# 12_MT7688AN_Power.net
KiCad netlist of a schematic drawn in Altium Designer
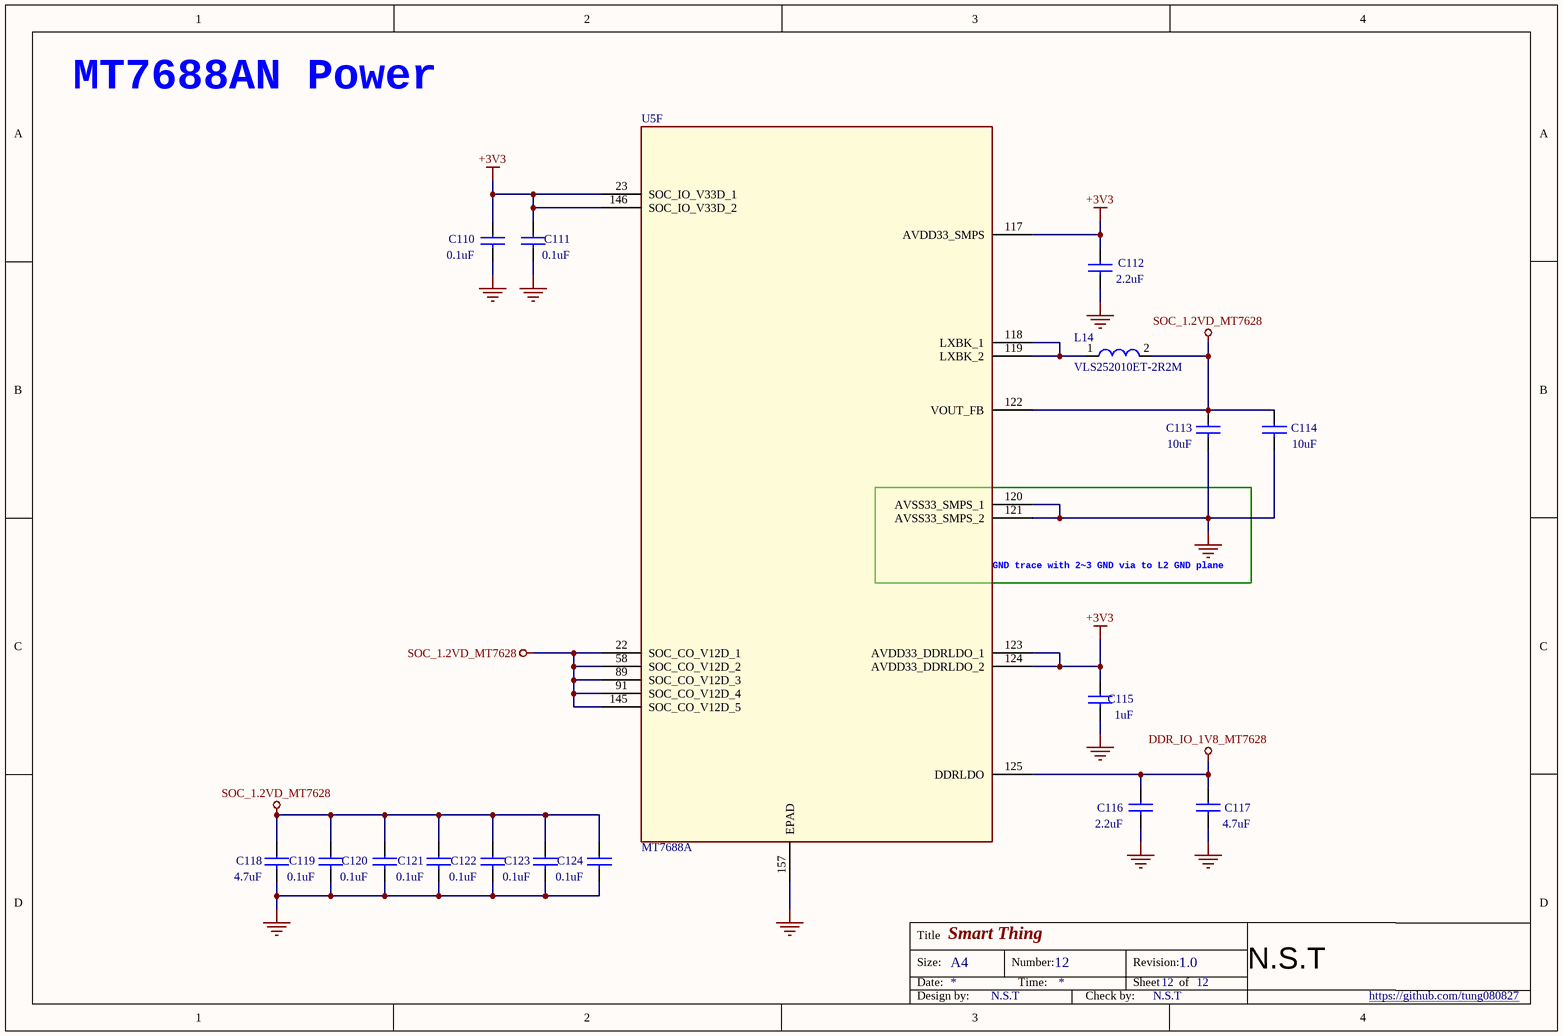
[diagram p0: 12. MT7688AN Power.SchDoc]

(export (version "E")
  (design (tool "Eeschema 10.0.6"))
  (components
    (comp (ref "C110")
      (value "0.1uF")
      (footprint "CAPC1005X55X25NL05T10")
      (libsource (lib "MT7688AN") (part "CAP NP"))
    )
    (comp (ref "C111")
      (value "0.1uF")
      (footprint "CAPC1005X55X25NL05T10")
      (libsource (lib "MT7688AN") (part "CAP NP"))
    )
    (comp (ref "C112")
      (value "2.2uF")
      (footprint "CAPC1608X90X35NL10T15")
      (libsource (lib "MT7688AN") (part "CAP NP"))
    )
    (comp (ref "C113")
      (value "10uF")
      (footprint "CAPC1608X90X35NL10T15")
      (libsource (lib "MT7688AN") (part "CAP NP"))
    )
    (comp (ref "C114")
      (value "10uF")
      (footprint "CAPC1608X90X35NL10T15")
      (libsource (lib "MT7688AN") (part "CAP NP"))
    )
    (comp (ref "C115")
      (value "1uF")
      (footprint "CAPC1608X90X35NL10T15")
      (libsource (lib "MT7688AN") (part "CAP NP"))
    )
    (comp (ref "C116")
      (value "2.2uF")
      (footprint "CAPC1608X90X35NL10T15")
      (libsource (lib "MT7688AN") (part "CAP NP"))
    )
    (comp (ref "C117")
      (value "4.7uF")
      (footprint "CAPC1005X55X25NL05T10")
      (libsource (lib "MT7688AN") (part "CAP NP"))
    )
    (comp (ref "C118")
      (value "4.7uF")
      (footprint "CAPC1005X55X25NL05T10")
      (libsource (lib "MT7688AN") (part "CAP NP"))
    )
    (comp (ref "C119")
      (value "0.1uF")
      (footprint "CAPC1005X55X25NL05T10")
      (libsource (lib "MT7688AN") (part "CAP NP"))
    )
    (comp (ref "C120")
      (value "0.1uF")
      (footprint "CAPC1005X55X25NL05T10")
      (libsource (lib "MT7688AN") (part "CAP NP"))
    )
    (comp (ref "C121")
      (value "0.1uF")
      (footprint "CAPC1005X55X25NL05T10")
      (libsource (lib "MT7688AN") (part "CAP NP"))
    )
    (comp (ref "C122")
      (value "0.1uF")
      (footprint "CAPC1005X55X25NL05T10")
      (libsource (lib "MT7688AN") (part "CAP NP"))
    )
    (comp (ref "C123")
      (value "0.1uF")
      (footprint "CAPC1005X55X25NL05T10")
      (libsource (lib "MT7688AN") (part "CAP NP"))
    )
    (comp (ref "C124")
      (value "0.1uF")
      (footprint "CAPC1005X55X25NL05T10")
      (libsource (lib "MT7688AN") (part "CAP NP"))
    )
    (comp (ref "L14")
      (value "VLS252010ET-2R2M")
      (footprint "VLS252010/TDK INDUCTOR")
      (description "IND 0805 METAL 2.2uH 0.19R 1.2A T=1.0mm")
      (libsource (lib "MT7688AN") (part "L/0402"))
    )
    (comp (ref "U5")
      (value "MT7688A")
      (footprint "MT7628AN$2F$DRQFN156$2F$SMD$2F$P0.5$2F$12X12")
      (libsource (lib "MT7688AN") (part "MT7620N-n_26"))
    )
  )
  (nets
    (net (code "1") (name "+3V3") (class "Default")
      (node (ref "C110") (pin "1") (pinfunction "1_1") (pintype "passive"))
      (node (ref "C111") (pin "1") (pinfunction "1_1") (pintype "passive"))
      (node (ref "C112") (pin "1") (pinfunction "1_1") (pintype "passive"))
      (node (ref "C115") (pin "1") (pinfunction "1_1") (pintype "passive"))
      (node (ref "U5") (pin "117") (pinfunction "AVDD33_SMPS_117") (pintype "power_in"))
      (node (ref "U5") (pin "123") (pinfunction "AVDD33_DDRLDO_1_123") (pintype "power_in"))
      (node (ref "U5") (pin "124") (pinfunction "AVDD33_DDRLDO_2_124") (pintype "power_in"))
      (node (ref "U5") (pin "146") (pinfunction "SOC_IO_V33D_2_146") (pintype "power_in"))
      (node (ref "U5") (pin "23") (pinfunction "SOC_IO_V33D_1_23") (pintype "power_in"))
    )
    (net (code "2") (name "DDR_IO_1V8_MT7628") (class "Default")
      (node (ref "C116") (pin "1") (pinfunction "1_1") (pintype "passive"))
      (node (ref "C117") (pin "1") (pinfunction "1_1") (pintype "passive"))
      (node (ref "U5") (pin "125") (pinfunction "DDRLDO_125") (pintype "power_in"))
    )
    (net (code "3") (name "GND") (class "Default")
      (node (ref "C110") (pin "2") (pinfunction "2_2") (pintype "passive"))
      (node (ref "C111") (pin "2") (pinfunction "2_2") (pintype "passive"))
      (node (ref "C112") (pin "2") (pinfunction "2_2") (pintype "passive"))
      (node (ref "C113") (pin "2") (pinfunction "2_2") (pintype "passive"))
      (node (ref "C114") (pin "2") (pinfunction "2_2") (pintype "passive"))
      (node (ref "C115") (pin "2") (pinfunction "2_2") (pintype "passive"))
      (node (ref "C116") (pin "2") (pinfunction "2_2") (pintype "passive"))
      (node (ref "C117") (pin "2") (pinfunction "2_2") (pintype "passive"))
      (node (ref "C118") (pin "2") (pinfunction "2_2") (pintype "passive"))
      (node (ref "C119") (pin "2") (pinfunction "2_2") (pintype "passive"))
      (node (ref "C120") (pin "2") (pinfunction "2_2") (pintype "passive"))
      (node (ref "C121") (pin "2") (pinfunction "2_2") (pintype "passive"))
      (node (ref "C122") (pin "2") (pinfunction "2_2") (pintype "passive"))
      (node (ref "C123") (pin "2") (pinfunction "2_2") (pintype "passive"))
      (node (ref "C124") (pin "2") (pinfunction "2_2") (pintype "passive"))
      (node (ref "U5") (pin "120") (pinfunction "AVSS33_SMPS_1_120") (pintype "power_in"))
      (node (ref "U5") (pin "121") (pinfunction "AVSS33_SMPS_2_121") (pintype "power_in"))
      (node (ref "U5") (pin "157") (pinfunction "EPAD_157") (pintype "power_in"))
    )
    (net (code "4") (name "Net-(U5F-LXBK_1)") (class "Default")
      (node (ref "L14") (pin "1") (pinfunction "1_1") (pintype "passive"))
      (node (ref "U5") (pin "118") (pinfunction "LXBK_1_118") (pintype "passive"))
      (node (ref "U5") (pin "119") (pinfunction "LXBK_2_119") (pintype "passive"))
    )
    (net (code "5") (name "SOC_1.2VD_MT7628") (class "Default")
      (node (ref "C113") (pin "1") (pinfunction "1_1") (pintype "passive"))
      (node (ref "C114") (pin "1") (pinfunction "1_1") (pintype "passive"))
      (node (ref "C118") (pin "1") (pinfunction "1_1") (pintype "passive"))
      (node (ref "C119") (pin "1") (pinfunction "1_1") (pintype "passive"))
      (node (ref "C120") (pin "1") (pinfunction "1_1") (pintype "passive"))
      (node (ref "C121") (pin "1") (pinfunction "1_1") (pintype "passive"))
      (node (ref "C122") (pin "1") (pinfunction "1_1") (pintype "passive"))
      (node (ref "C123") (pin "1") (pinfunction "1_1") (pintype "passive"))
      (node (ref "C124") (pin "1") (pinfunction "1_1") (pintype "passive"))
      (node (ref "L14") (pin "2") (pinfunction "2_2") (pintype "passive"))
      (node (ref "U5") (pin "122") (pinfunction "VOUT_FB_122") (pintype "power_in"))
      (node (ref "U5") (pin "145") (pinfunction "SOC_CO_V12D_5_145") (pintype "power_in"))
      (node (ref "U5") (pin "22") (pinfunction "SOC_CO_V12D_1_22") (pintype "power_in"))
      (node (ref "U5") (pin "58") (pinfunction "SOC_CO_V12D_2_58") (pintype "power_in"))
      (node (ref "U5") (pin "89") (pinfunction "SOC_CO_V12D_3_89") (pintype "power_in"))
      (node (ref "U5") (pin "91") (pinfunction "SOC_CO_V12D_4_91") (pintype "power_in"))
    )
  )
)
